# 03_electrode_interface.net
KiCad netlist of a schematic drawn in Altium Designer
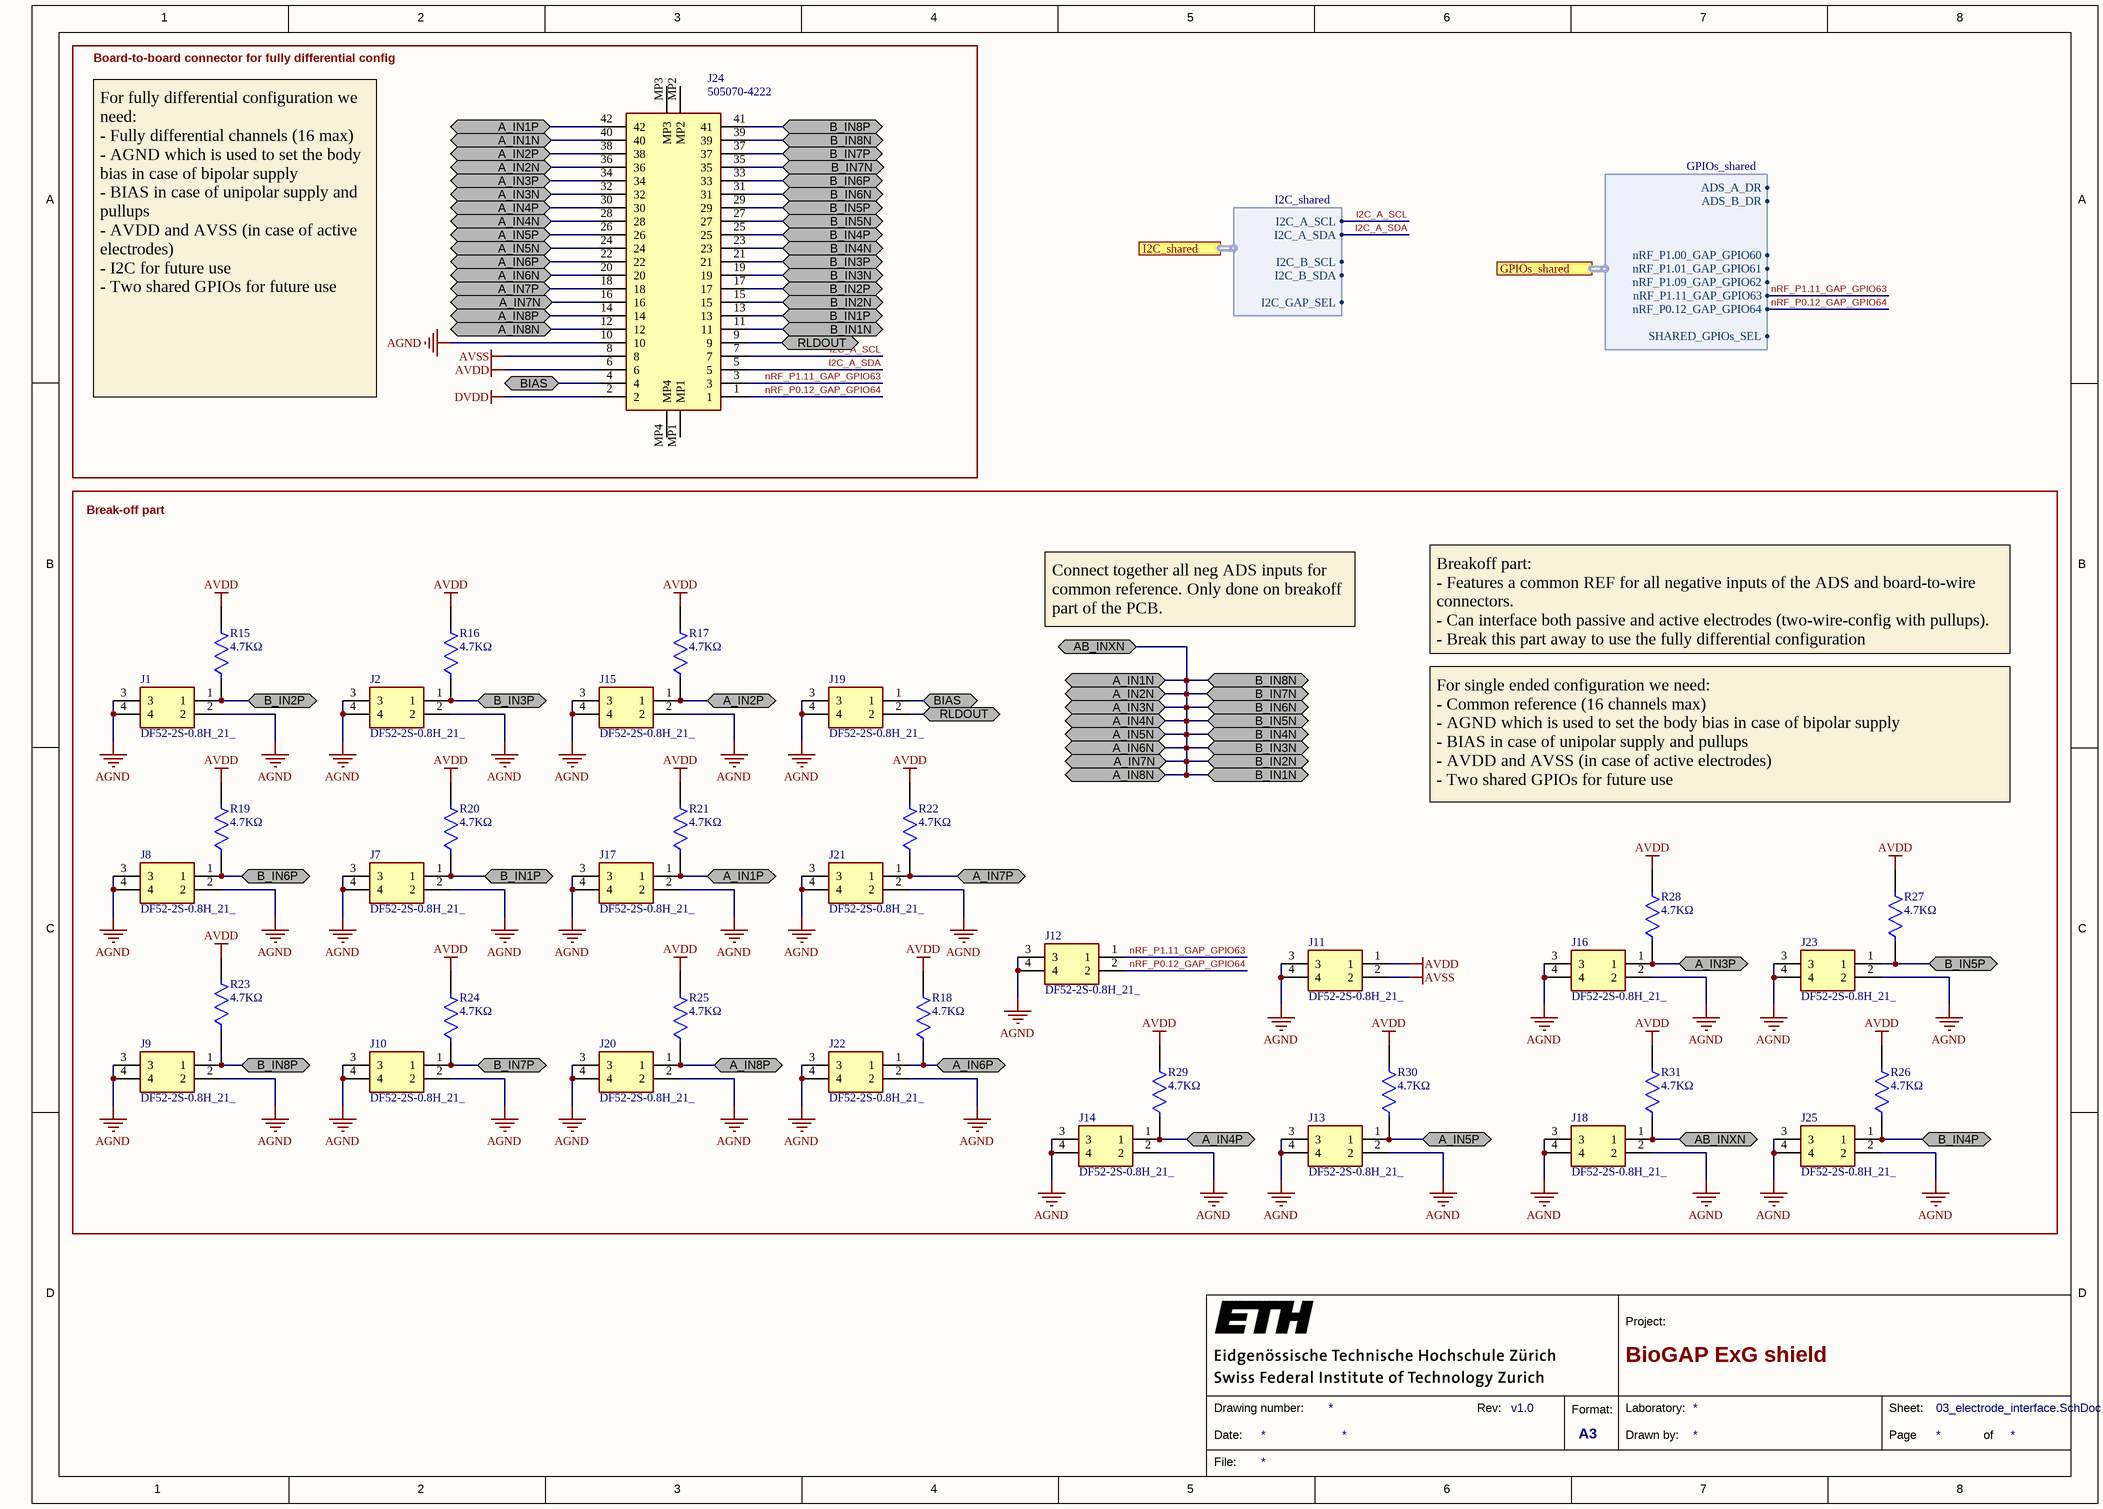
[diagram p0: 03_electrode_interface.SchDoc]

(export (version "E")
  (design (tool "Eeschema 10.0.6"))
  (components
    (comp (ref "J1")
      (value "DF52-2S-0.8H_21_")
      (footprint "SamacSys:DF522S08H21")
      (description "Connector")
      (fields
        (field (name "MANUFACTURER_PART_NUMBER") "DF52-2S-0.8H(21)")
        (field (name "MOUSER PART NUMBER") "798-DF52-2S-0.8H21")
      )
      (libsource (lib "SamacSys") (part "DF52-2S-0.8H_21_"))
    )
    (comp (ref "J2")
      (value "DF52-2S-0.8H_21_")
      (footprint "SamacSys:DF522S08H21")
      (description "Connector")
      (fields
        (field (name "MANUFACTURER_PART_NUMBER") "DF52-2S-0.8H(21)")
        (field (name "MOUSER PART NUMBER") "798-DF52-2S-0.8H21")
      )
      (libsource (lib "SamacSys") (part "DF52-2S-0.8H_21_"))
    )
    (comp (ref "J7")
      (value "DF52-2S-0.8H_21_")
      (footprint "SamacSys:DF522S08H21")
      (description "Connector")
      (fields
        (field (name "MANUFACTURER_PART_NUMBER") "DF52-2S-0.8H(21)")
        (field (name "MOUSER PART NUMBER") "798-DF52-2S-0.8H21")
      )
      (libsource (lib "SamacSys") (part "DF52-2S-0.8H_21_"))
    )
    (comp (ref "J8")
      (value "DF52-2S-0.8H_21_")
      (footprint "SamacSys:DF522S08H21")
      (description "Connector")
      (fields
        (field (name "MANUFACTURER_PART_NUMBER") "DF52-2S-0.8H(21)")
        (field (name "MOUSER PART NUMBER") "798-DF52-2S-0.8H21")
      )
      (libsource (lib "SamacSys") (part "DF52-2S-0.8H_21_"))
    )
    (comp (ref "J9")
      (value "DF52-2S-0.8H_21_")
      (footprint "SamacSys:DF522S08H21")
      (description "Connector")
      (fields
        (field (name "MANUFACTURER_PART_NUMBER") "DF52-2S-0.8H(21)")
        (field (name "MOUSER PART NUMBER") "798-DF52-2S-0.8H21")
      )
      (libsource (lib "SamacSys") (part "DF52-2S-0.8H_21_"))
    )
    (comp (ref "J10")
      (value "DF52-2S-0.8H_21_")
      (footprint "SamacSys:DF522S08H21")
      (description "Connector")
      (fields
        (field (name "MANUFACTURER_PART_NUMBER") "DF52-2S-0.8H(21)")
        (field (name "MOUSER PART NUMBER") "798-DF52-2S-0.8H21")
      )
      (libsource (lib "SamacSys") (part "DF52-2S-0.8H_21_"))
    )
    (comp (ref "J11")
      (value "DF52-2S-0.8H_21_")
      (footprint "SamacSys:DF522S08H21")
      (description "Connector")
      (fields
        (field (name "MANUFACTURER_PART_NUMBER") "DF52-2S-0.8H(21)")
        (field (name "MOUSER PART NUMBER") "798-DF52-2S-0.8H21")
      )
      (libsource (lib "SamacSys") (part "DF52-2S-0.8H_21_"))
    )
    (comp (ref "J12")
      (value "DF52-2S-0.8H_21_")
      (footprint "SamacSys:DF522S08H21")
      (description "Connector")
      (fields
        (field (name "MANUFACTURER_PART_NUMBER") "DF52-2S-0.8H(21)")
        (field (name "MOUSER PART NUMBER") "798-DF52-2S-0.8H21")
      )
      (libsource (lib "SamacSys") (part "DF52-2S-0.8H_21_"))
    )
    (comp (ref "J13")
      (value "DF52-2S-0.8H_21_")
      (footprint "SamacSys:DF522S08H21")
      (description "Connector")
      (fields
        (field (name "MANUFACTURER_PART_NUMBER") "DF52-2S-0.8H(21)")
        (field (name "MOUSER PART NUMBER") "798-DF52-2S-0.8H21")
      )
      (libsource (lib "SamacSys") (part "DF52-2S-0.8H_21_"))
    )
    (comp (ref "J14")
      (value "DF52-2S-0.8H_21_")
      (footprint "SamacSys:DF522S08H21")
      (description "Connector")
      (fields
        (field (name "MANUFACTURER_PART_NUMBER") "DF52-2S-0.8H(21)")
        (field (name "MOUSER PART NUMBER") "798-DF52-2S-0.8H21")
      )
      (libsource (lib "SamacSys") (part "DF52-2S-0.8H_21_"))
    )
    (comp (ref "J15")
      (value "DF52-2S-0.8H_21_")
      (footprint "SamacSys:DF522S08H21")
      (description "Connector")
      (fields
        (field (name "MANUFACTURER_PART_NUMBER") "DF52-2S-0.8H(21)")
        (field (name "MOUSER PART NUMBER") "798-DF52-2S-0.8H21")
      )
      (libsource (lib "SamacSys") (part "DF52-2S-0.8H_21_"))
    )
    (comp (ref "J16")
      (value "DF52-2S-0.8H_21_")
      (footprint "SamacSys:DF522S08H21")
      (description "Connector")
      (fields
        (field (name "MANUFACTURER_PART_NUMBER") "DF52-2S-0.8H(21)")
        (field (name "MOUSER PART NUMBER") "798-DF52-2S-0.8H21")
      )
      (libsource (lib "SamacSys") (part "DF52-2S-0.8H_21_"))
    )
    (comp (ref "J17")
      (value "DF52-2S-0.8H_21_")
      (footprint "SamacSys:DF522S08H21")
      (description "Connector")
      (fields
        (field (name "MANUFACTURER_PART_NUMBER") "DF52-2S-0.8H(21)")
        (field (name "MOUSER PART NUMBER") "798-DF52-2S-0.8H21")
      )
      (libsource (lib "SamacSys") (part "DF52-2S-0.8H_21_"))
    )
    (comp (ref "J18")
      (value "DF52-2S-0.8H_21_")
      (footprint "SamacSys:DF522S08H21")
      (description "Connector")
      (fields
        (field (name "MANUFACTURER_PART_NUMBER") "DF52-2S-0.8H(21)")
        (field (name "MOUSER PART NUMBER") "798-DF52-2S-0.8H21")
      )
      (libsource (lib "SamacSys") (part "DF52-2S-0.8H_21_"))
    )
    (comp (ref "J19")
      (value "DF52-2S-0.8H_21_")
      (footprint "SamacSys:DF522S08H21")
      (description "Connector")
      (fields
        (field (name "MANUFACTURER_PART_NUMBER") "DF52-2S-0.8H(21)")
        (field (name "MOUSER PART NUMBER") "798-DF52-2S-0.8H21")
      )
      (libsource (lib "SamacSys") (part "DF52-2S-0.8H_21_"))
    )
    (comp (ref "J20")
      (value "DF52-2S-0.8H_21_")
      (footprint "SamacSys:DF522S08H21")
      (description "Connector")
      (fields
        (field (name "MANUFACTURER_PART_NUMBER") "DF52-2S-0.8H(21)")
        (field (name "MOUSER PART NUMBER") "798-DF52-2S-0.8H21")
      )
      (libsource (lib "SamacSys") (part "DF52-2S-0.8H_21_"))
    )
    (comp (ref "J21")
      (value "DF52-2S-0.8H_21_")
      (footprint "SamacSys:DF522S08H21")
      (description "Connector")
      (fields
        (field (name "MANUFACTURER_PART_NUMBER") "DF52-2S-0.8H(21)")
        (field (name "MOUSER PART NUMBER") "798-DF52-2S-0.8H21")
      )
      (libsource (lib "SamacSys") (part "DF52-2S-0.8H_21_"))
    )
    (comp (ref "J22")
      (value "DF52-2S-0.8H_21_")
      (footprint "SamacSys:DF522S08H21")
      (description "Connector")
      (fields
        (field (name "MANUFACTURER_PART_NUMBER") "DF52-2S-0.8H(21)")
        (field (name "MOUSER PART NUMBER") "798-DF52-2S-0.8H21")
      )
      (libsource (lib "SamacSys") (part "DF52-2S-0.8H_21_"))
    )
    (comp (ref "J23")
      (value "DF52-2S-0.8H_21_")
      (footprint "SamacSys:DF522S08H21")
      (description "Connector")
      (fields
        (field (name "MANUFACTURER_PART_NUMBER") "DF52-2S-0.8H(21)")
        (field (name "MOUSER PART NUMBER") "798-DF52-2S-0.8H21")
      )
      (libsource (lib "SamacSys") (part "DF52-2S-0.8H_21_"))
    )
    (comp (ref "J24")
      (value "505070-4222")
      (footprint "SamacSys:5050704222")
      (description "Connector")
      (fields
        (field (name "MANUFACTURER_PART_NUMBER") "505070-4022")
        (field (name "MOUSER PART NUMBER") "538-505070-4022")
      )
      (libsource (lib "SamacSys") (part "505070-4222"))
    )
    (comp (ref "J25")
      (value "DF52-2S-0.8H_21_")
      (footprint "SamacSys:DF522S08H21")
      (description "Connector")
      (fields
        (field (name "MANUFACTURER_PART_NUMBER") "DF52-2S-0.8H(21)")
        (field (name "MOUSER PART NUMBER") "798-DF52-2S-0.8H21")
      )
      (libsource (lib "SamacSys") (part "DF52-2S-0.8H_21_"))
    )
    (comp (ref "R15")
      (value "4.7KΩ")
      (footprint "FP-RT0402-MFG")
      (description "RES 4.70K OHM 1/16W 1% SMD 0402")
      (fields
        (field (name "MANUFACTURER PART NUMBER") "RT0402FRE074K7L")
        (field (name "MANUFACTURER") "Yageo")
      )
      (libsource (lib "Altium Content Vault") (part "1029c3af85768c4190bb7ad29bc67b5"))
    )
    (comp (ref "R16")
      (value "4.7KΩ")
      (footprint "FP-RT0402-MFG")
      (description "RES 4.70K OHM 1/16W 1% SMD 0402")
      (fields
        (field (name "MANUFACTURER PART NUMBER") "RT0402FRE074K7L")
        (field (name "MANUFACTURER") "Yageo")
      )
      (libsource (lib "Altium Content Vault") (part "1029c3af85768c4190bb7ad29bc67b5"))
    )
    (comp (ref "R17")
      (value "4.7KΩ")
      (footprint "FP-RT0402-MFG")
      (description "RES 4.70K OHM 1/16W 1% SMD 0402")
      (fields
        (field (name "MANUFACTURER PART NUMBER") "RT0402FRE074K7L")
        (field (name "MANUFACTURER") "Yageo")
      )
      (libsource (lib "Altium Content Vault") (part "1029c3af85768c4190bb7ad29bc67b5"))
    )
    (comp (ref "R18")
      (value "4.7KΩ")
      (footprint "FP-RT0402-MFG")
      (description "RES 4.70K OHM 1/16W 1% SMD 0402")
      (fields
        (field (name "MANUFACTURER PART NUMBER") "RT0402FRE074K7L")
        (field (name "MANUFACTURER") "Yageo")
      )
      (libsource (lib "Altium Content Vault") (part "1029c3af85768c4190bb7ad29bc67b5"))
    )
    (comp (ref "R19")
      (value "4.7KΩ")
      (footprint "FP-RT0402-MFG")
      (description "RES 4.70K OHM 1/16W 1% SMD 0402")
      (fields
        (field (name "MANUFACTURER PART NUMBER") "RT0402FRE074K7L")
        (field (name "MANUFACTURER") "Yageo")
      )
      (libsource (lib "Altium Content Vault") (part "1029c3af85768c4190bb7ad29bc67b5"))
    )
    (comp (ref "R20")
      (value "4.7KΩ")
      (footprint "FP-RT0402-MFG")
      (description "RES 4.70K OHM 1/16W 1% SMD 0402")
      (fields
        (field (name "MANUFACTURER PART NUMBER") "RT0402FRE074K7L")
        (field (name "MANUFACTURER") "Yageo")
      )
      (libsource (lib "Altium Content Vault") (part "1029c3af85768c4190bb7ad29bc67b5"))
    )
    (comp (ref "R21")
      (value "4.7KΩ")
      (footprint "FP-RT0402-MFG")
      (description "RES 4.70K OHM 1/16W 1% SMD 0402")
      (fields
        (field (name "MANUFACTURER PART NUMBER") "RT0402FRE074K7L")
        (field (name "MANUFACTURER") "Yageo")
      )
      (libsource (lib "Altium Content Vault") (part "1029c3af85768c4190bb7ad29bc67b5"))
    )
    (comp (ref "R22")
      (value "4.7KΩ")
      (footprint "FP-RT0402-MFG")
      (description "RES 4.70K OHM 1/16W 1% SMD 0402")
      (fields
        (field (name "MANUFACTURER PART NUMBER") "RT0402FRE074K7L")
        (field (name "MANUFACTURER") "Yageo")
      )
      (libsource (lib "Altium Content Vault") (part "1029c3af85768c4190bb7ad29bc67b5"))
    )
    (comp (ref "R23")
      (value "4.7KΩ")
      (footprint "FP-RT0402-MFG")
      (description "RES 4.70K OHM 1/16W 1% SMD 0402")
      (fields
        (field (name "MANUFACTURER PART NUMBER") "RT0402FRE074K7L")
        (field (name "MANUFACTURER") "Yageo")
      )
      (libsource (lib "Altium Content Vault") (part "1029c3af85768c4190bb7ad29bc67b5"))
    )
    (comp (ref "R24")
      (value "4.7KΩ")
      (footprint "FP-RT0402-MFG")
      (description "RES 4.70K OHM 1/16W 1% SMD 0402")
      (fields
        (field (name "MANUFACTURER PART NUMBER") "RT0402FRE074K7L")
        (field (name "MANUFACTURER") "Yageo")
      )
      (libsource (lib "Altium Content Vault") (part "1029c3af85768c4190bb7ad29bc67b5"))
    )
    (comp (ref "R25")
      (value "4.7KΩ")
      (footprint "FP-RT0402-MFG")
      (description "RES 4.70K OHM 1/16W 1% SMD 0402")
      (fields
        (field (name "MANUFACTURER PART NUMBER") "RT0402FRE074K7L")
        (field (name "MANUFACTURER") "Yageo")
      )
      (libsource (lib "Altium Content Vault") (part "1029c3af85768c4190bb7ad29bc67b5"))
    )
    (comp (ref "R26")
      (value "4.7KΩ")
      (footprint "FP-RT0402-MFG")
      (description "RES 4.70K OHM 1/16W 1% SMD 0402")
      (fields
        (field (name "MANUFACTURER PART NUMBER") "RT0402FRE074K7L")
        (field (name "MANUFACTURER") "Yageo")
      )
      (libsource (lib "Altium Content Vault") (part "1029c3af85768c4190bb7ad29bc67b5"))
    )
    (comp (ref "R27")
      (value "4.7KΩ")
      (footprint "FP-RT0402-MFG")
      (description "RES 4.70K OHM 1/16W 1% SMD 0402")
      (fields
        (field (name "MANUFACTURER PART NUMBER") "RT0402FRE074K7L")
        (field (name "MANUFACTURER") "Yageo")
      )
      (libsource (lib "Altium Content Vault") (part "1029c3af85768c4190bb7ad29bc67b5"))
    )
    (comp (ref "R28")
      (value "4.7KΩ")
      (footprint "FP-RT0402-MFG")
      (description "RES 4.70K OHM 1/16W 1% SMD 0402")
      (fields
        (field (name "MANUFACTURER PART NUMBER") "RT0402FRE074K7L")
        (field (name "MANUFACTURER") "Yageo")
      )
      (libsource (lib "Altium Content Vault") (part "1029c3af85768c4190bb7ad29bc67b5"))
    )
    (comp (ref "R29")
      (value "4.7KΩ")
      (footprint "FP-RT0402-MFG")
      (description "RES 4.70K OHM 1/16W 1% SMD 0402")
      (fields
        (field (name "MANUFACTURER PART NUMBER") "RT0402FRE074K7L")
        (field (name "MANUFACTURER") "Yageo")
      )
      (libsource (lib "Altium Content Vault") (part "1029c3af85768c4190bb7ad29bc67b5"))
    )
    (comp (ref "R30")
      (value "4.7KΩ")
      (footprint "FP-RT0402-MFG")
      (description "RES 4.70K OHM 1/16W 1% SMD 0402")
      (fields
        (field (name "MANUFACTURER PART NUMBER") "RT0402FRE074K7L")
        (field (name "MANUFACTURER") "Yageo")
      )
      (libsource (lib "Altium Content Vault") (part "1029c3af85768c4190bb7ad29bc67b5"))
    )
    (comp (ref "R31")
      (value "4.7KΩ")
      (footprint "FP-RT0402-MFG")
      (description "RES 4.70K OHM 1/16W 1% SMD 0402")
      (fields
        (field (name "MANUFACTURER PART NUMBER") "RT0402FRE074K7L")
        (field (name "MANUFACTURER") "Yageo")
      )
      (libsource (lib "Altium Content Vault") (part "1029c3af85768c4190bb7ad29bc67b5"))
    )
  )
  (nets
    (net (code "3") (name "/AB_INXN") (class "Default")
      (node (ref "J18") (pin "1") (pinfunction "1_1") (pintype "passive"))
      (node (ref "J24") (pin "11") (pinfunction "11_11") (pintype "passive"))
      (node (ref "J24") (pin "12") (pinfunction "12_12") (pintype "passive"))
      (node (ref "J24") (pin "15") (pinfunction "15_15") (pintype "passive"))
      (node (ref "J24") (pin "16") (pinfunction "16_16") (pintype "passive"))
      (node (ref "J24") (pin "19") (pinfunction "19_19") (pintype "passive"))
      (node (ref "J24") (pin "20") (pinfunction "20_20") (pintype "passive"))
      (node (ref "J24") (pin "23") (pinfunction "23_23") (pintype "passive"))
      (node (ref "J24") (pin "24") (pinfunction "24_24") (pintype "passive"))
      (node (ref "J24") (pin "27") (pinfunction "27_27") (pintype "passive"))
      (node (ref "J24") (pin "28") (pinfunction "28_28") (pintype "passive"))
      (node (ref "J24") (pin "31") (pinfunction "31_31") (pintype "passive"))
      (node (ref "J24") (pin "32") (pinfunction "32_32") (pintype "passive"))
      (node (ref "J24") (pin "35") (pinfunction "35_35") (pintype "passive"))
      (node (ref "J24") (pin "36") (pinfunction "36_36") (pintype "passive"))
      (node (ref "J24") (pin "39") (pinfunction "39_39") (pintype "passive"))
      (node (ref "J24") (pin "40") (pinfunction "40_40") (pintype "passive"))
      (node (ref "R31") (pin "1") (pinfunction "1_1") (pintype "passive"))
    )
    (net (code "4") (name "/A_IN1P") (class "Default")
      (node (ref "J17") (pin "1") (pinfunction "1_1") (pintype "passive"))
      (node (ref "J24") (pin "42") (pinfunction "42_42") (pintype "passive"))
      (node (ref "R21") (pin "1") (pinfunction "1_1") (pintype "passive"))
    )
    (net (code "5") (name "/A_IN2P") (class "Default")
      (node (ref "J15") (pin "1") (pinfunction "1_1") (pintype "passive"))
      (node (ref "J24") (pin "38") (pinfunction "38_38") (pintype "passive"))
      (node (ref "R17") (pin "1") (pinfunction "1_1") (pintype "passive"))
    )
    (net (code "6") (name "/A_IN3P") (class "Default")
      (node (ref "J16") (pin "1") (pinfunction "1_1") (pintype "passive"))
      (node (ref "J24") (pin "34") (pinfunction "34_34") (pintype "passive"))
      (node (ref "R28") (pin "1") (pinfunction "1_1") (pintype "passive"))
    )
    (net (code "7") (name "/A_IN4P") (class "Default")
      (node (ref "J14") (pin "1") (pinfunction "1_1") (pintype "passive"))
      (node (ref "J24") (pin "30") (pinfunction "30_30") (pintype "passive"))
      (node (ref "R29") (pin "1") (pinfunction "1_1") (pintype "passive"))
    )
    (net (code "8") (name "/A_IN5P") (class "Default")
      (node (ref "J13") (pin "1") (pinfunction "1_1") (pintype "passive"))
      (node (ref "J24") (pin "26") (pinfunction "26_26") (pintype "passive"))
      (node (ref "R30") (pin "1") (pinfunction "1_1") (pintype "passive"))
    )
    (net (code "9") (name "/A_IN6P") (class "Default")
      (node (ref "J22") (pin "1") (pinfunction "1_1") (pintype "passive"))
      (node (ref "J24") (pin "22") (pinfunction "22_22") (pintype "passive"))
      (node (ref "R18") (pin "1") (pinfunction "1_1") (pintype "passive"))
    )
    (net (code "10") (name "/A_IN7P") (class "Default")
      (node (ref "J21") (pin "1") (pinfunction "1_1") (pintype "passive"))
      (node (ref "J24") (pin "18") (pinfunction "18_18") (pintype "passive"))
      (node (ref "R22") (pin "1") (pinfunction "1_1") (pintype "passive"))
    )
    (net (code "11") (name "/A_IN8P") (class "Default")
      (node (ref "J20") (pin "1") (pinfunction "1_1") (pintype "passive"))
      (node (ref "J24") (pin "14") (pinfunction "14_14") (pintype "passive"))
      (node (ref "R25") (pin "1") (pinfunction "1_1") (pintype "passive"))
    )
    (net (code "12") (name "/BIAS") (class "Default")
      (node (ref "J19") (pin "1") (pinfunction "1_1") (pintype "passive"))
      (node (ref "J24") (pin "4") (pinfunction "4_4") (pintype "passive"))
    )
    (net (code "13") (name "/B_IN1P") (class "Default")
      (node (ref "J24") (pin "13") (pinfunction "13_13") (pintype "passive"))
      (node (ref "J7") (pin "1") (pinfunction "1_1") (pintype "passive"))
      (node (ref "R20") (pin "1") (pinfunction "1_1") (pintype "passive"))
    )
    (net (code "14") (name "/B_IN2P") (class "Default")
      (node (ref "J1") (pin "1") (pinfunction "1_1") (pintype "passive"))
      (node (ref "J24") (pin "17") (pinfunction "17_17") (pintype "passive"))
      (node (ref "R15") (pin "1") (pinfunction "1_1") (pintype "passive"))
    )
    (net (code "15") (name "/B_IN3P") (class "Default")
      (node (ref "J2") (pin "1") (pinfunction "1_1") (pintype "passive"))
      (node (ref "J24") (pin "21") (pinfunction "21_21") (pintype "passive"))
      (node (ref "R16") (pin "1") (pinfunction "1_1") (pintype "passive"))
    )
    (net (code "16") (name "/B_IN4P") (class "Default")
      (node (ref "J24") (pin "25") (pinfunction "25_25") (pintype "passive"))
      (node (ref "J25") (pin "1") (pinfunction "1_1") (pintype "passive"))
      (node (ref "R26") (pin "1") (pinfunction "1_1") (pintype "passive"))
    )
    (net (code "17") (name "/B_IN5P") (class "Default")
      (node (ref "J23") (pin "1") (pinfunction "1_1") (pintype "passive"))
      (node (ref "J24") (pin "29") (pinfunction "29_29") (pintype "passive"))
      (node (ref "R27") (pin "1") (pinfunction "1_1") (pintype "passive"))
    )
    (net (code "18") (name "/B_IN6P") (class "Default")
      (node (ref "J24") (pin "33") (pinfunction "33_33") (pintype "passive"))
      (node (ref "J8") (pin "1") (pinfunction "1_1") (pintype "passive"))
      (node (ref "R19") (pin "1") (pinfunction "1_1") (pintype "passive"))
    )
    (net (code "19") (name "/B_IN7P") (class "Default")
      (node (ref "J10") (pin "1") (pinfunction "1_1") (pintype "passive"))
      (node (ref "J24") (pin "37") (pinfunction "37_37") (pintype "passive"))
      (node (ref "R24") (pin "1") (pinfunction "1_1") (pintype "passive"))
    )
    (net (code "20") (name "/B_IN8P") (class "Default")
      (node (ref "J24") (pin "41") (pinfunction "41_41") (pintype "passive"))
      (node (ref "J9") (pin "1") (pinfunction "1_1") (pintype "passive"))
      (node (ref "R23") (pin "1") (pinfunction "1_1") (pintype "passive"))
    )
    (net (code "21") (name "/I2C_A_SCL") (class "Default")
      (node (ref "J24") (pin "7") (pinfunction "7_7") (pintype "passive"))
    )
    (net (code "22") (name "/I2C_A_SDA") (class "Default")
      (node (ref "J24") (pin "5") (pinfunction "5_5") (pintype "passive"))
    )
    (net (code "23") (name "/RLDOUT") (class "Default")
      (node (ref "J19") (pin "2") (pinfunction "2_2") (pintype "passive"))
      (node (ref "J24") (pin "9") (pinfunction "9_9") (pintype "passive"))
    )
    (net (code "24") (name "/nRF_P0.12_GAP_GPIO64") (class "Default")
      (node (ref "J12") (pin "2") (pinfunction "2_2") (pintype "passive"))
      (node (ref "J24") (pin "1") (pinfunction "1_1") (pintype "passive"))
    )
    (net (code "25") (name "/nRF_P1.11_GAP_GPIO63") (class "Default")
      (node (ref "J12") (pin "1") (pinfunction "1_1") (pintype "passive"))
      (node (ref "J24") (pin "3") (pinfunction "3_3") (pintype "passive"))
    )
    (net (code "28") (name "AGND") (class "Default")
      (node (ref "J1") (pin "2") (pinfunction "2_2") (pintype "passive"))
      (node (ref "J1") (pin "3") (pinfunction "3_3") (pintype "passive"))
      (node (ref "J1") (pin "4") (pinfunction "4_4") (pintype "passive"))
      (node (ref "J10") (pin "2") (pinfunction "2_2") (pintype "passive"))
      (node (ref "J10") (pin "3") (pinfunction "3_3") (pintype "passive"))
      (node (ref "J10") (pin "4") (pinfunction "4_4") (pintype "passive"))
      (node (ref "J11") (pin "3") (pinfunction "3_3") (pintype "passive"))
      (node (ref "J11") (pin "4") (pinfunction "4_4") (pintype "passive"))
      (node (ref "J12") (pin "3") (pinfunction "3_3") (pintype "passive"))
      (node (ref "J12") (pin "4") (pinfunction "4_4") (pintype "passive"))
      (node (ref "J13") (pin "2") (pinfunction "2_2") (pintype "passive"))
      (node (ref "J13") (pin "3") (pinfunction "3_3") (pintype "passive"))
      (node (ref "J13") (pin "4") (pinfunction "4_4") (pintype "passive"))
      (node (ref "J14") (pin "2") (pinfunction "2_2") (pintype "passive"))
      (node (ref "J14") (pin "3") (pinfunction "3_3") (pintype "passive"))
      (node (ref "J14") (pin "4") (pinfunction "4_4") (pintype "passive"))
      (node (ref "J15") (pin "2") (pinfunction "2_2") (pintype "passive"))
      (node (ref "J15") (pin "3") (pinfunction "3_3") (pintype "passive"))
      (node (ref "J15") (pin "4") (pinfunction "4_4") (pintype "passive"))
      (node (ref "J16") (pin "2") (pinfunction "2_2") (pintype "passive"))
      (node (ref "J16") (pin "3") (pinfunction "3_3") (pintype "passive"))
      (node (ref "J16") (pin "4") (pinfunction "4_4") (pintype "passive"))
      (node (ref "J17") (pin "2") (pinfunction "2_2") (pintype "passive"))
      (node (ref "J17") (pin "3") (pinfunction "3_3") (pintype "passive"))
      (node (ref "J17") (pin "4") (pinfunction "4_4") (pintype "passive"))
      (node (ref "J18") (pin "2") (pinfunction "2_2") (pintype "passive"))
      (node (ref "J18") (pin "3") (pinfunction "3_3") (pintype "passive"))
      (node (ref "J18") (pin "4") (pinfunction "4_4") (pintype "passive"))
      (node (ref "J19") (pin "3") (pinfunction "3_3") (pintype "passive"))
      (node (ref "J19") (pin "4") (pinfunction "4_4") (pintype "passive"))
      (node (ref "J2") (pin "2") (pinfunction "2_2") (pintype "passive"))
      (node (ref "J2") (pin "3") (pinfunction "3_3") (pintype "passive"))
      (node (ref "J2") (pin "4") (pinfunction "4_4") (pintype "passive"))
      (node (ref "J20") (pin "2") (pinfunction "2_2") (pintype "passive"))
      (node (ref "J20") (pin "3") (pinfunction "3_3") (pintype "passive"))
      (node (ref "J20") (pin "4") (pinfunction "4_4") (pintype "passive"))
      (node (ref "J21") (pin "2") (pinfunction "2_2") (pintype "passive"))
      (node (ref "J21") (pin "3") (pinfunction "3_3") (pintype "passive"))
      (node (ref "J21") (pin "4") (pinfunction "4_4") (pintype "passive"))
      (node (ref "J22") (pin "2") (pinfunction "2_2") (pintype "passive"))
      (node (ref "J22") (pin "3") (pinfunction "3_3") (pintype "passive"))
      (node (ref "J22") (pin "4") (pinfunction "4_4") (pintype "passive"))
      (node (ref "J23") (pin "2") (pinfunction "2_2") (pintype "passive"))
      (node (ref "J23") (pin "3") (pinfunction "3_3") (pintype "passive"))
      (node (ref "J23") (pin "4") (pinfunction "4_4") (pintype "passive"))
      (node (ref "J24") (pin "10") (pinfunction "10_10") (pintype "passive"))
      (node (ref "J25") (pin "2") (pinfunction "2_2") (pintype "passive"))
      (node (ref "J25") (pin "3") (pinfunction "3_3") (pintype "passive"))
      (node (ref "J25") (pin "4") (pinfunction "4_4") (pintype "passive"))
      (node (ref "J7") (pin "2") (pinfunction "2_2") (pintype "passive"))
      (node (ref "J7") (pin "3") (pinfunction "3_3") (pintype "passive"))
      (node (ref "J7") (pin "4") (pinfunction "4_4") (pintype "passive"))
      (node (ref "J8") (pin "2") (pinfunction "2_2") (pintype "passive"))
      (node (ref "J8") (pin "3") (pinfunction "3_3") (pintype "passive"))
      (node (ref "J8") (pin "4") (pinfunction "4_4") (pintype "passive"))
      (node (ref "J9") (pin "2") (pinfunction "2_2") (pintype "passive"))
      (node (ref "J9") (pin "3") (pinfunction "3_3") (pintype "passive"))
      (node (ref "J9") (pin "4") (pinfunction "4_4") (pintype "passive"))
    )
    (net (code "29") (name "AVDD") (class "Default")
      (node (ref "J11") (pin "1") (pinfunction "1_1") (pintype "passive"))
      (node (ref "J24") (pin "6") (pinfunction "6_6") (pintype "passive"))
      (node (ref "R15") (pin "2") (pinfunction "2_2") (pintype "passive"))
      (node (ref "R16") (pin "2") (pinfunction "2_2") (pintype "passive"))
      (node (ref "R17") (pin "2") (pinfunction "2_2") (pintype "passive"))
      (node (ref "R18") (pin "2") (pinfunction "2_2") (pintype "passive"))
      (node (ref "R19") (pin "2") (pinfunction "2_2") (pintype "passive"))
      (node (ref "R20") (pin "2") (pinfunction "2_2") (pintype "passive"))
      (node (ref "R21") (pin "2") (pinfunction "2_2") (pintype "passive"))
      (node (ref "R22") (pin "2") (pinfunction "2_2") (pintype "passive"))
      (node (ref "R23") (pin "2") (pinfunction "2_2") (pintype "passive"))
      (node (ref "R24") (pin "2") (pinfunction "2_2") (pintype "passive"))
      (node (ref "R25") (pin "2") (pinfunction "2_2") (pintype "passive"))
      (node (ref "R26") (pin "2") (pinfunction "2_2") (pintype "passive"))
      (node (ref "R27") (pin "2") (pinfunction "2_2") (pintype "passive"))
      (node (ref "R28") (pin "2") (pinfunction "2_2") (pintype "passive"))
      (node (ref "R29") (pin "2") (pinfunction "2_2") (pintype "passive"))
      (node (ref "R30") (pin "2") (pinfunction "2_2") (pintype "passive"))
      (node (ref "R31") (pin "2") (pinfunction "2_2") (pintype "passive"))
    )
    (net (code "30") (name "AVSS") (class "Default")
      (node (ref "J11") (pin "2") (pinfunction "2_2") (pintype "passive"))
      (node (ref "J24") (pin "8") (pinfunction "8_8") (pintype "passive"))
    )
    (net (code "31") (name "DVDD") (class "Default")
      (node (ref "J24") (pin "2") (pinfunction "2_2") (pintype "passive"))
    )
    (net (code "32") (name "unconnected-(J24-PadMP1)") (class "Default")
      (node (ref "J24") (pin "MP1") (pinfunction "MP1_MP1") (pintype "passive"))
    )
    (net (code "33") (name "unconnected-(J24-PadMP2)") (class "Default")
      (node (ref "J24") (pin "MP2") (pinfunction "MP2_MP2") (pintype "passive"))
    )
    (net (code "34") (name "unconnected-(J24-PadMP3)") (class "Default")
      (node (ref "J24") (pin "MP3") (pinfunction "MP3_MP3") (pintype "passive"))
    )
    (net (code "35") (name "unconnected-(J24-PadMP4)") (class "Default")
      (node (ref "J24") (pin "MP4") (pinfunction "MP4_MP4") (pintype "passive"))
    )
  )
)
